# SCH_555-circuit_2026-01-02.net
KiCad netlist of a schematic drawn in EasyEDA
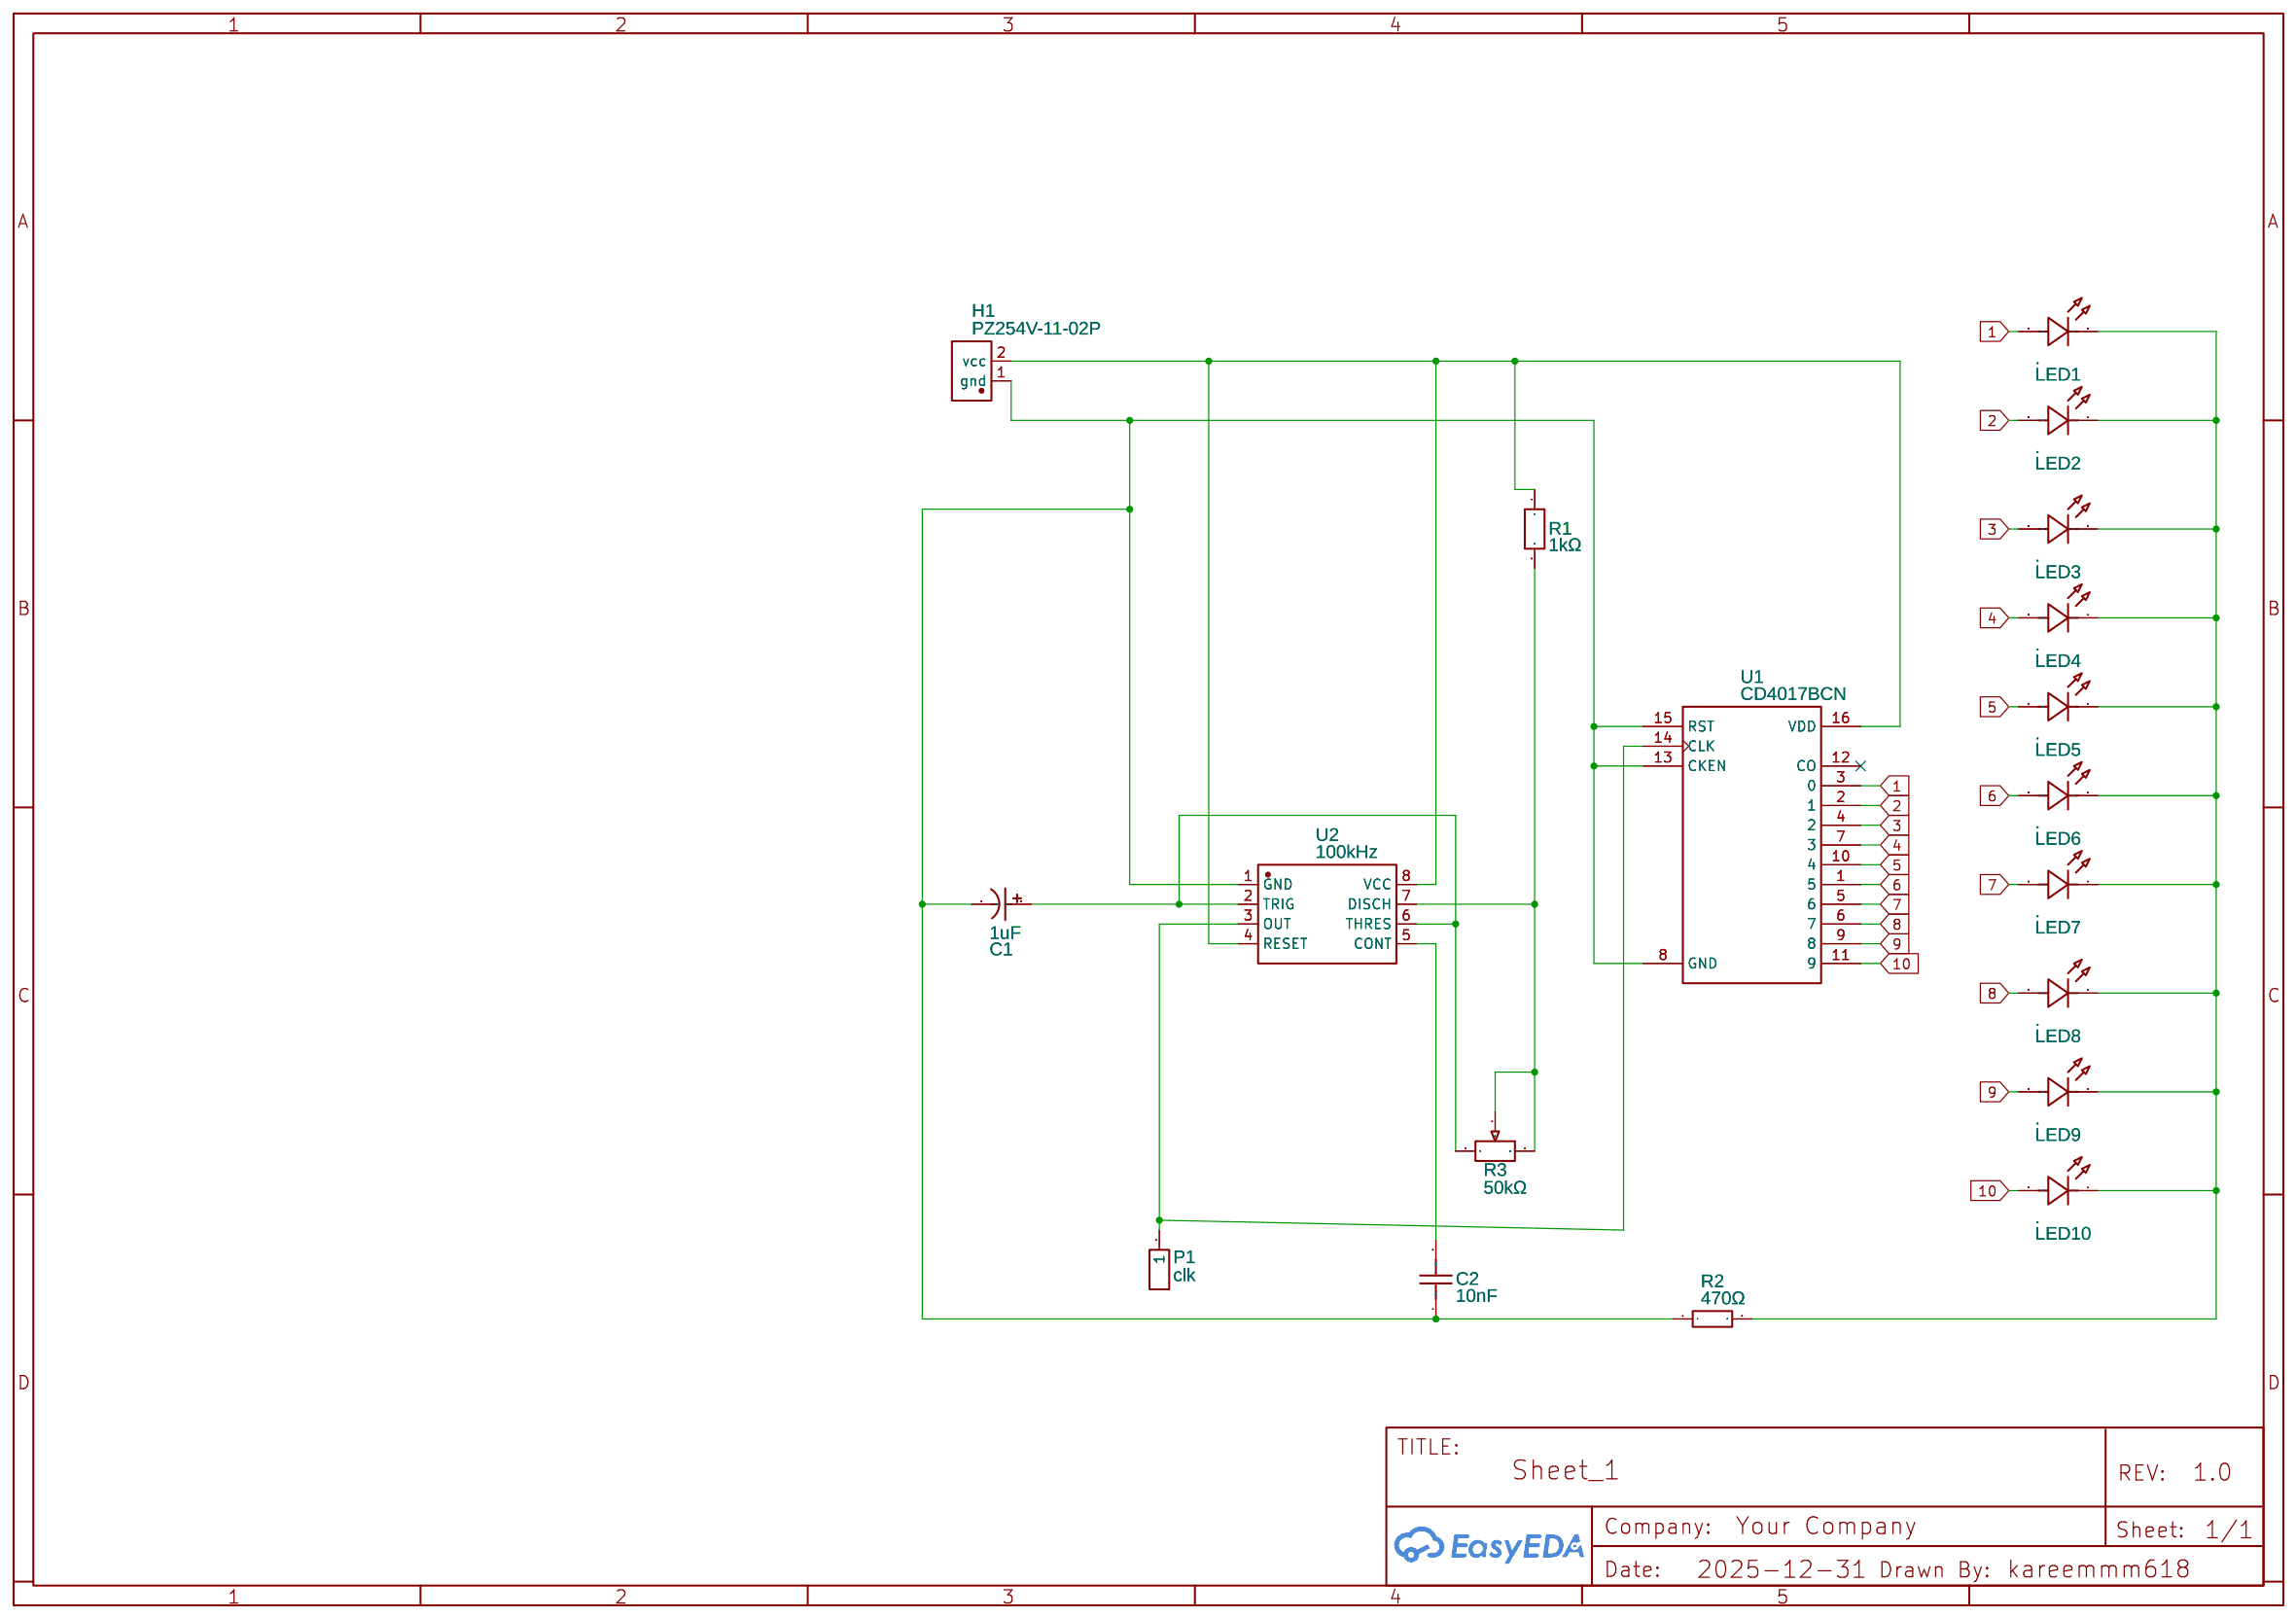
[diagram p0: schematic sheet]

(export (version "E")
  (design (tool "Eeschema 10.0.6"))
  (components
    (comp (ref "C1")
      (value "1uF")
      (fields (field (name "Manufacturer Part") "KF010M050C110A") (field (name "Manufacturer") "CapXon(丰宾)"))
      (libsource (lib "") (part "KF010M050C110A"))
    )
    (comp (ref "C2")
      (value "10nF")
      (fields (field (name "Manufacturer Part") "N09F1B103MN0B0S0N0") (field (name "Manufacturer") "STE(松田)"))
      (libsource (lib "") (part "N09F1B103MN0B0S0N0"))
    )
    (comp (ref "H1")
      (value "PZ254V-11-02P")
      (fields (field (name "Manufacturer") "XFCN(兴飞)"))
      (libsource (lib "") (part "PZ254V-11-02P"))
    )
    (comp (ref "LED1")
      (value ".")
      (fields (field (name "Manufacturer Part") "XL-502UWC") (field (name "Manufacturer") "XINGLIGHT(成兴光)"))
      (libsource (lib "") (part "XL-502UWC"))
    )
    (comp (ref "LED2")
      (value ".")
      (fields (field (name "Manufacturer Part") "XL-502UWC") (field (name "Manufacturer") "XINGLIGHT(成兴光)"))
      (libsource (lib "") (part "XL-502UWC"))
    )
    (comp (ref "LED3")
      (value ".")
      (fields (field (name "Manufacturer Part") "XL-502UWC") (field (name "Manufacturer") "XINGLIGHT(成兴光)"))
      (libsource (lib "") (part "XL-502UWC"))
    )
    (comp (ref "LED4")
      (value ".")
      (fields (field (name "Manufacturer Part") "XL-502UWC") (field (name "Manufacturer") "XINGLIGHT(成兴光)"))
      (libsource (lib "") (part "XL-502UWC"))
    )
    (comp (ref "LED5")
      (value ".")
      (fields (field (name "Manufacturer Part") "XL-502UWC") (field (name "Manufacturer") "XINGLIGHT(成兴光)"))
      (libsource (lib "") (part "XL-502UWC"))
    )
    (comp (ref "LED6")
      (value ".")
      (fields (field (name "Manufacturer Part") "XL-502UWC") (field (name "Manufacturer") "XINGLIGHT(成兴光)"))
      (libsource (lib "") (part "XL-502UWC"))
    )
    (comp (ref "LED7")
      (value ".")
      (fields (field (name "Manufacturer Part") "XL-502UWC") (field (name "Manufacturer") "XINGLIGHT(成兴光)"))
      (libsource (lib "") (part "XL-502UWC"))
    )
    (comp (ref "LED8")
      (value ".")
      (fields (field (name "Manufacturer Part") "XL-502UWC") (field (name "Manufacturer") "XINGLIGHT(成兴光)"))
      (libsource (lib "") (part "XL-502UWC"))
    )
    (comp (ref "LED9")
      (value ".")
      (fields (field (name "Manufacturer Part") "XL-502UWC") (field (name "Manufacturer") "XINGLIGHT(成兴光)"))
      (libsource (lib "") (part "XL-502UWC"))
    )
    (comp (ref "LED10")
      (value ".")
      (fields (field (name "Manufacturer Part") "XL-502UWC") (field (name "Manufacturer") "XINGLIGHT(成兴光)"))
      (libsource (lib "") (part "XL-502UWC"))
    )
    (comp (ref "P1")
      (value "clk")
      (fields (field (name "Manufacturer Part") "2.54-1*1P针") (field (name "Manufacturer") "BOOMELE(博穆精密)"))
      (libsource (lib "") (part "Header-Male-2.54_1x1"))
    )
    (comp (ref "R1")
      (value "1kΩ")
      (fields (field (name "Manufacturer Part") "MF1/4W-1KΩ±1%T52") (field (name "Manufacturer") "华星机电"))
      (libsource (lib "") (part "MF1/4W-1KΩ±1%T52"))
    )
    (comp (ref "R2")
      (value "470Ω")
      (fields
        (field (name "Manufacturer Part") "MFR0W4F4700A50")
        (field (name "Manufacturer") "UNI-ROYAL(厚声)")
      )
      (libsource (lib "") (part "MFR0W4F4700A50"))
    )
    (comp (ref "R3")
      (value "50kΩ")
      (fields (field (name "Manufacturer Part") "3296X-1-503") (field (name "Manufacturer") "BOCHEN(博晨)"))
      (libsource (lib "") (part "3296X-1-503_C118912"))
    )
    (comp (ref "U1") (value "CD4017BCN") (libsource (lib "") (part "CD4017BCN")))
    (comp (ref "U2")
      (value "100kHz")
      (fields (field (name "Manufacturer Part") "NE555P") (field (name "Manufacturer") "TI(德州仪器)"))
      (libsource (lib "") (part "NE555P"))
    )
  )
  (nets
    (net (code "1") (name "1") (class "Default")
      (node (ref "LED1") (pin "2") (pinfunction "A_2") (pintype "unspecified"))
      (node (ref "U1") (pin "3") (pinfunction "0_3") (pintype "output"))
    )
    (net (code "2") (name "2") (class "Default")
      (node (ref "LED2") (pin "2") (pinfunction "A_2") (pintype "unspecified"))
      (node (ref "U1") (pin "2") (pinfunction "1_2") (pintype "output"))
    )
    (net (code "3") (name "3") (class "Default")
      (node (ref "LED3") (pin "2") (pinfunction "A_2") (pintype "unspecified"))
      (node (ref "U1") (pin "4") (pinfunction "2_4") (pintype "output"))
    )
    (net (code "4") (name "4") (class "Default")
      (node (ref "LED4") (pin "2") (pinfunction "A_2") (pintype "unspecified"))
      (node (ref "U1") (pin "7") (pinfunction "3_7") (pintype "output"))
    )
    (net (code "5") (name "5") (class "Default")
      (node (ref "LED5") (pin "2") (pinfunction "A_2") (pintype "unspecified"))
      (node (ref "U1") (pin "10") (pinfunction "4_10") (pintype "output"))
    )
    (net (code "6") (name "6") (class "Default")
      (node (ref "LED6") (pin "2") (pinfunction "A_2") (pintype "unspecified"))
      (node (ref "U1") (pin "1") (pinfunction "5_1") (pintype "output"))
    )
    (net (code "7") (name "7") (class "Default")
      (node (ref "LED7") (pin "2") (pinfunction "A_2") (pintype "unspecified"))
      (node (ref "U1") (pin "5") (pinfunction "6_5") (pintype "output"))
    )
    (net (code "8") (name "8") (class "Default")
      (node (ref "LED8") (pin "2") (pinfunction "A_2") (pintype "unspecified"))
      (node (ref "U1") (pin "6") (pinfunction "7_6") (pintype "output"))
    )
    (net (code "9") (name "9") (class "Default")
      (node (ref "LED9") (pin "2") (pinfunction "A_2") (pintype "unspecified"))
      (node (ref "U1") (pin "9") (pinfunction "8_9") (pintype "output"))
    )
    (net (code "10") (name "10") (class "Default")
      (node (ref "LED10") (pin "2") (pinfunction "A_2") (pintype "unspecified"))
      (node (ref "U1") (pin "11") (pinfunction "9_11") (pintype "output"))
    )
    (net (code "11") (name "Net-(H1-gnd)") (class "Default")
      (node (ref "C1") (pin "2") (pinfunction "2_2") (pintype "input"))
      (node (ref "C2") (pin "1") (pinfunction "1_1") (pintype "unspecified"))
      (node (ref "H1") (pin "1") (pinfunction "gnd_1") (pintype "unspecified"))
      (node (ref "R2") (pin "1") (pinfunction "1_1") (pintype "input"))
      (node (ref "U1") (pin "13") (pinfunction "CKEN_13") (pintype "unspecified"))
      (node (ref "U1") (pin "15") (pinfunction "RST_15") (pintype "unspecified"))
      (node (ref "U1") (pin "8") (pinfunction "GND_8") (pintype "passive"))
      (node (ref "U2") (pin "1") (pinfunction "GND_1") (pintype "unspecified"))
    )
    (net (code "12") (name "Net-(H1-vcc)") (class "Default")
      (node (ref "H1") (pin "2") (pinfunction "vcc_2") (pintype "unspecified"))
      (node (ref "R1") (pin "1") (pinfunction "1_1") (pintype "unspecified"))
      (node (ref "U1") (pin "16") (pinfunction "VDD_16") (pintype "passive"))
      (node (ref "U2") (pin "4") (pinfunction "RESET_4") (pintype "unspecified"))
      (node (ref "U2") (pin "8") (pinfunction "VCC_8") (pintype "unspecified"))
    )
    (net (code "13") (name "Net-(LED1-K)") (class "Default")
      (node (ref "LED1") (pin "1") (pinfunction "K_1") (pintype "unspecified"))
      (node (ref "LED10") (pin "1") (pinfunction "K_1") (pintype "unspecified"))
      (node (ref "LED2") (pin "1") (pinfunction "K_1") (pintype "unspecified"))
      (node (ref "LED3") (pin "1") (pinfunction "K_1") (pintype "unspecified"))
      (node (ref "LED4") (pin "1") (pinfunction "K_1") (pintype "unspecified"))
      (node (ref "LED5") (pin "1") (pinfunction "K_1") (pintype "unspecified"))
      (node (ref "LED6") (pin "1") (pinfunction "K_1") (pintype "unspecified"))
      (node (ref "LED7") (pin "1") (pinfunction "K_1") (pintype "unspecified"))
      (node (ref "LED8") (pin "1") (pinfunction "K_1") (pintype "unspecified"))
      (node (ref "LED9") (pin "1") (pinfunction "K_1") (pintype "unspecified"))
      (node (ref "R2") (pin "2") (pinfunction "2_2") (pintype "input"))
    )
    (net (code "14") (name "Net-(U1-CLK)") (class "Default")
      (node (ref "P1") (pin "1") (pinfunction "1_1") (pintype "input"))
      (node (ref "U1") (pin "14") (pinfunction "CLK_14") (pintype "unspecified"))
      (node (ref "U2") (pin "3") (pinfunction "OUT_3") (pintype "unspecified"))
    )
    (net (code "15") (name "Net-(U2-CONT)") (class "Default")
      (node (ref "C2") (pin "2") (pinfunction "2_2") (pintype "unspecified"))
      (node (ref "U2") (pin "5") (pinfunction "CONT_5") (pintype "unspecified"))
    )
    (net (code "16") (name "Net-(U2-DISCH)") (class "Default")
      (node (ref "R1") (pin "2") (pinfunction "2_2") (pintype "unspecified"))
      (node (ref "R3") (pin "2") (pinfunction "2_2") (pintype "input"))
      (node (ref "R3") (pin "3") (pinfunction "3_3") (pintype "input"))
      (node (ref "U2") (pin "7") (pinfunction "DISCH_7") (pintype "unspecified"))
    )
    (net (code "17") (name "Net-(U2-THRES)") (class "Default")
      (node (ref "C1") (pin "1") (pinfunction "1_1") (pintype "input"))
      (node (ref "R3") (pin "1") (pinfunction "1_1") (pintype "input"))
      (node (ref "U2") (pin "2") (pinfunction "TRIG_2") (pintype "unspecified"))
      (node (ref "U2") (pin "6") (pinfunction "THRES_6") (pintype "unspecified"))
    )
    (net (code "18") (name "unconnected-(U1-CO-Pad12)") (class "Default")
      (node (ref "U1") (pin "12") (pinfunction "CO_12") (pintype "output+no_connect"))
    )
  )
)
